# tmtr_board_rev1_1.net
KiCad netlist of a schematic drawn in Altium Designer
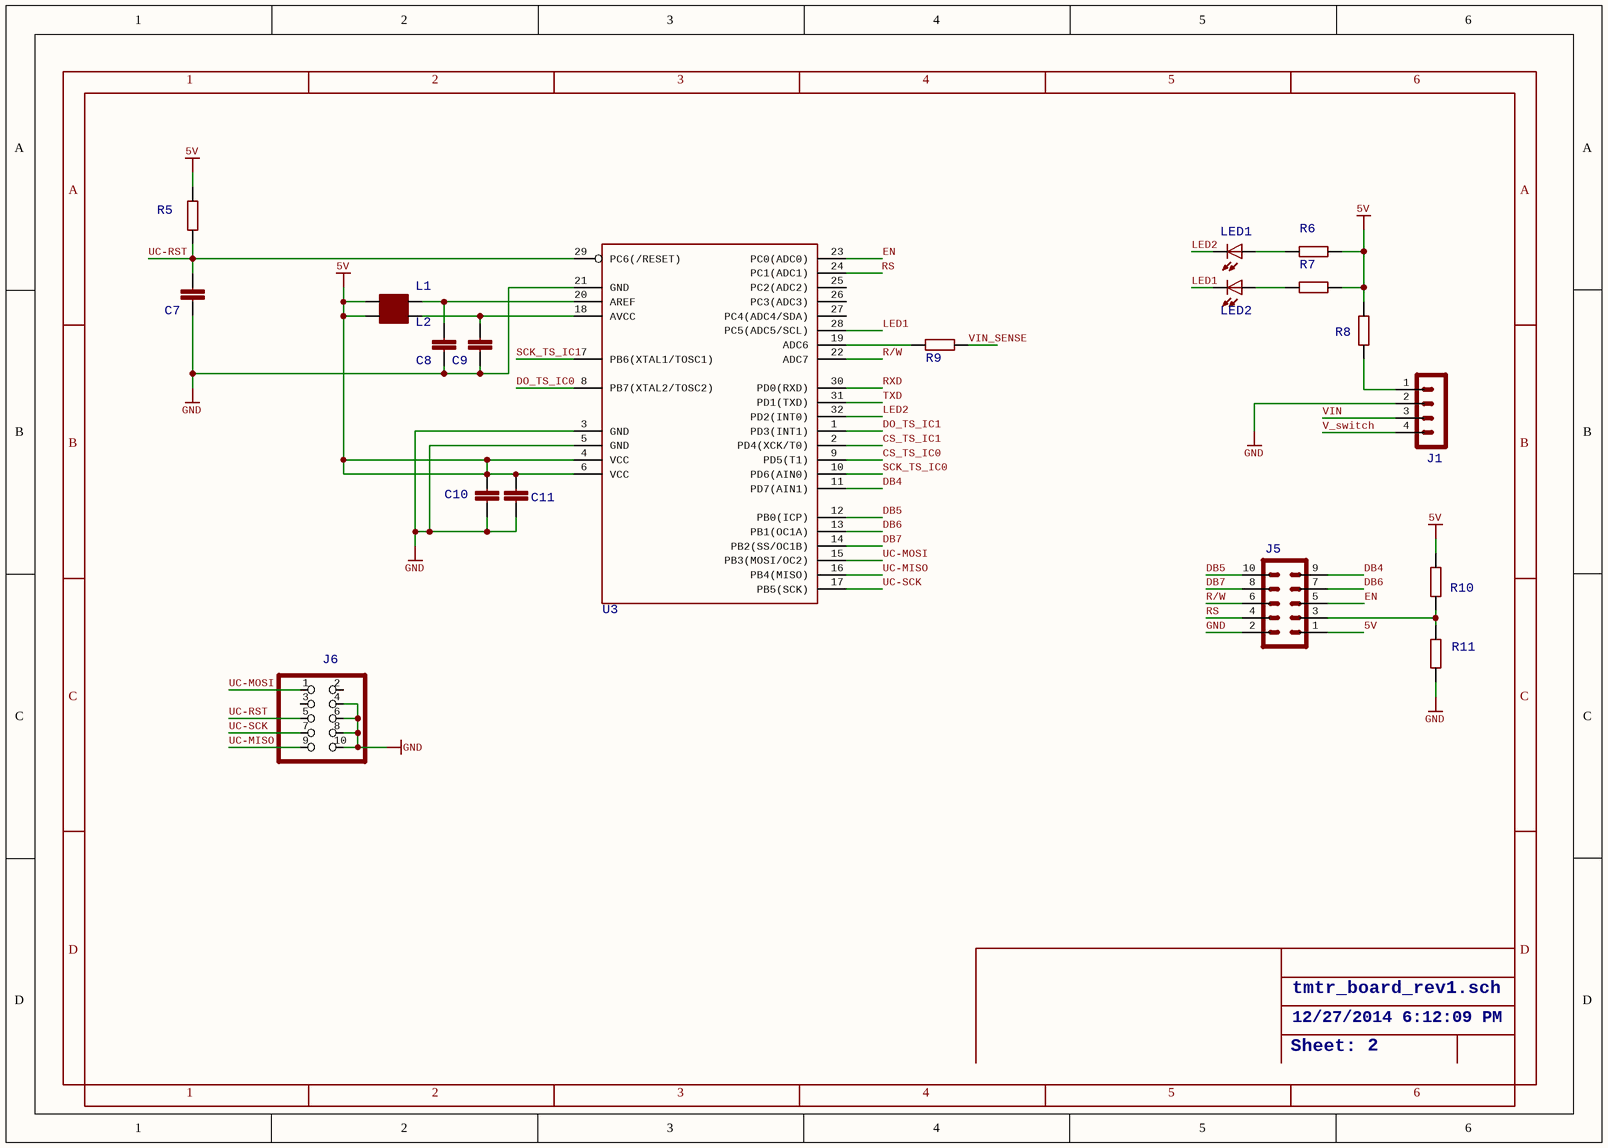
[diagram p0: tmtr_board_rev1_1.SchDoc]

(export (version "E")
  (design (tool "Eeschema 10.0.6"))
  (components
    (comp (ref "C7")
      (value "CAP0805")
      (footprint "0805")
      (description "<b>Capacitor</b>\nStandard 0603 ceramic capacitor, and 0.1\" leaded capacitor.")
      (libsource (lib "SparkFun1") (part "CAP0805"))
    )
    (comp (ref "C8")
      (value "CAP0805")
      (footprint "0805")
      (description "<b>Capacitor</b>\nStandard 0603 ceramic capacitor, and 0.1\" leaded capacitor.")
      (libsource (lib "SparkFun1") (part "CAP0805"))
    )
    (comp (ref "C9")
      (value "CAP0805")
      (footprint "0805")
      (description "<b>Capacitor</b>\nStandard 0603 ceramic capacitor, and 0.1\" leaded capacitor.")
      (libsource (lib "SparkFun1") (part "CAP0805"))
    )
    (comp (ref "C10")
      (value "CAP0805")
      (footprint "0805")
      (description "<b>Capacitor</b>\nStandard 0603 ceramic capacitor, and 0.1\" leaded capacitor.")
      (libsource (lib "SparkFun1") (part "CAP0805"))
    )
    (comp (ref "C11")
      (value "CAP0805")
      (footprint "0805")
      (description "<b>Capacitor</b>\nStandard 0603 ceramic capacitor, and 0.1\" leaded capacitor.")
      (libsource (lib "SparkFun1") (part "CAP0805"))
    )
    (comp (ref "J1")
      (value "<b>PIN HEADER</b>")
      (footprint "MA04-1")
      (libsource (lib "con-lstb") (part "MA04-1"))
    )
    (comp (ref "J5")
      (value "<b>PIN HEADER</b>")
      (footprint "MA05-2")
      (libsource (lib "con-lstb") (part "MA05-2"))
    )
    (comp (ref "J6")
      (value "AVR_SPI_PROG")
      (footprint "AVR_ICSP")
      (libsource (lib "SparkFun2") (part "AVR_SPI_PROG"))
    )
    (comp (ref "L1")
      (value "WE-CBF_0805")
      (footprint "0805")
      (libsource (lib "wuerth-elektronik") (part "WE-CBF_0805"))
    )
    (comp (ref "L2")
      (value "WE-CBF_0805")
      (footprint "0805")
      (libsource (lib "wuerth-elektronik") (part "WE-CBF_0805"))
    )
    (comp (ref "LED1")
      (value "LEDCHIPLED_0805")
      (footprint "CHIPLED_0805")
      (libsource (lib "led") (part "LEDCHIPLED_0805"))
    )
    (comp (ref "LED2")
      (value "LEDCHIPLED_0805")
      (footprint "CHIPLED_0805")
      (libsource (lib "led") (part "LEDCHIPLED_0805"))
    )
    (comp (ref "R5")
      (value "R-EU_R0805W")
      (footprint "R0805W")
      (description "<B>RESISTOR</B>, European symbol")
      (libsource (lib "resistor") (part "R-EU_R0805W"))
    )
    (comp (ref "R6")
      (value "R-EU_M0805")
      (footprint "M0805")
      (description "<B>RESISTOR</B>, European symbol")
      (libsource (lib "resistor") (part "R-EU_M0805"))
    )
    (comp (ref "R7")
      (value "R-EU_M0805")
      (footprint "M0805")
      (description "<B>RESISTOR</B>, European symbol")
      (libsource (lib "resistor") (part "R-EU_M0805"))
    )
    (comp (ref "R8")
      (value "R-EU_M0805")
      (footprint "M0805")
      (description "<B>RESISTOR</B>, European symbol")
      (libsource (lib "resistor") (part "R-EU_M0805"))
    )
    (comp (ref "R9")
      (value "R-EU_M0805")
      (footprint "M0805")
      (description "<B>RESISTOR</B>, European symbol")
      (libsource (lib "resistor") (part "R-EU_M0805"))
    )
    (comp (ref "R10")
      (value "R-EU_M0805")
      (footprint "M0805")
      (description "<B>RESISTOR</B>, European symbol")
      (libsource (lib "resistor") (part "R-EU_M0805"))
    )
    (comp (ref "R11")
      (value "R-EU_M0805")
      (footprint "M0805")
      (description "<B>RESISTOR</B>, European symbol")
      (libsource (lib "resistor") (part "R-EU_M0805"))
    )
    (comp (ref "U3") (value "MEGA8-AI") (footprint "TQFP32-08") (libsource (lib "atmel") (part "MEGA8-AI")))
  )
  (nets
    (net (code "1") (name "/CS_TS_IC0") (class "Default")
      (node (ref "U3") (pin "9") (pinfunction "PD5(T1)_9") (pintype "passive"))
    )
    (net (code "2") (name "/CS_TS_IC1") (class "Default")
      (node (ref "U3") (pin "2") (pinfunction "PD4(XCK/T0)_2") (pintype "passive"))
    )
    (net (code "3") (name "/DB4") (class "Default")
      (node (ref "J5") (pin "9") (pinfunction "9_9") (pintype "passive"))
      (node (ref "U3") (pin "11") (pinfunction "PD7(AIN1)_11") (pintype "passive"))
    )
    (net (code "4") (name "/DB5") (class "Default")
      (node (ref "J5") (pin "10") (pinfunction "10_10") (pintype "passive"))
      (node (ref "U3") (pin "12") (pinfunction "PB0(ICP)_12") (pintype "passive"))
    )
    (net (code "5") (name "/DB6") (class "Default")
      (node (ref "J5") (pin "7") (pinfunction "7_7") (pintype "passive"))
      (node (ref "U3") (pin "13") (pinfunction "PB1(OC1A)_13") (pintype "passive"))
    )
    (net (code "6") (name "/DB7") (class "Default")
      (node (ref "J5") (pin "8") (pinfunction "8_8") (pintype "passive"))
      (node (ref "U3") (pin "14") (pinfunction "PB2(SS/OC1B)_14") (pintype "passive"))
    )
    (net (code "7") (name "/DO_TS_IC0") (class "Default")
      (node (ref "U3") (pin "8") (pinfunction "PB7(XTAL2/TOSC2)_8") (pintype "passive"))
    )
    (net (code "8") (name "/DO_TS_IC1") (class "Default")
      (node (ref "U3") (pin "1") (pinfunction "PD3(INT1)_1") (pintype "passive"))
    )
    (net (code "9") (name "/EN") (class "Default")
      (node (ref "J5") (pin "5") (pinfunction "5_5") (pintype "passive"))
      (node (ref "U3") (pin "23") (pinfunction "PC0(ADC0)_23") (pintype "passive"))
    )
    (net (code "10") (name "/LED1") (class "Default")
      (node (ref "LED2") (pin "C") (pinfunction "C_C") (pintype "passive"))
      (node (ref "U3") (pin "28") (pinfunction "PC5(ADC5/SCL)_28") (pintype "passive"))
    )
    (net (code "11") (name "/LED2") (class "Default")
      (node (ref "LED1") (pin "C") (pinfunction "C_C") (pintype "passive"))
      (node (ref "U3") (pin "32") (pinfunction "PD2(INT0)_32") (pintype "passive"))
    )
    (net (code "12") (name "/RS") (class "Default")
      (node (ref "J5") (pin "4") (pinfunction "4_4") (pintype "passive"))
      (node (ref "U3") (pin "24") (pinfunction "PC1(ADC1)_24") (pintype "passive"))
    )
    (net (code "13") (name "/RXD") (class "Default")
      (node (ref "U3") (pin "30") (pinfunction "PD0(RXD)_30") (pintype "passive"))
    )
    (net (code "14") (name "/R{slash}W") (class "Default")
      (node (ref "J5") (pin "6") (pinfunction "6_6") (pintype "passive"))
      (node (ref "U3") (pin "22") (pinfunction "ADC7_22") (pintype "passive"))
    )
    (net (code "15") (name "/SCK_TS_IC0") (class "Default")
      (node (ref "U3") (pin "10") (pinfunction "PD6(AIN0)_10") (pintype "passive"))
    )
    (net (code "16") (name "/SCK_TS_IC1") (class "Default")
      (node (ref "U3") (pin "7") (pinfunction "PB6(XTAL1/TOSC1)_7") (pintype "passive"))
    )
    (net (code "17") (name "/TXD") (class "Default")
      (node (ref "U3") (pin "31") (pinfunction "PD1(TXD)_31") (pintype "passive"))
    )
    (net (code "18") (name "/UC-MISO") (class "Default")
      (node (ref "J6") (pin "9") (pinfunction "9_9") (pintype "passive"))
      (node (ref "U3") (pin "16") (pinfunction "PB4(MISO)_16") (pintype "passive"))
    )
    (net (code "19") (name "/UC-MOSI") (class "Default")
      (node (ref "J6") (pin "1") (pinfunction "1_1") (pintype "passive"))
      (node (ref "U3") (pin "15") (pinfunction "PB3(MOSI/OC2)_15") (pintype "passive"))
    )
    (net (code "20") (name "/UC-RST") (class "Default")
      (node (ref "C7") (pin "2") (pinfunction "2_2") (pintype "passive"))
      (node (ref "J6") (pin "5") (pinfunction "5_5") (pintype "passive"))
      (node (ref "R5") (pin "1") (pinfunction "1_1") (pintype "passive"))
      (node (ref "U3") (pin "29") (pinfunction "PC6(/RESET)_29") (pintype "passive"))
    )
    (net (code "21") (name "/UC-SCK") (class "Default")
      (node (ref "J6") (pin "7") (pinfunction "7_7") (pintype "passive"))
      (node (ref "U3") (pin "17") (pinfunction "PB5(SCK)_17") (pintype "passive"))
    )
    (net (code "22") (name "/VIN") (class "Default")
      (node (ref "J1") (pin "3") (pinfunction "3_3") (pintype "passive"))
    )
    (net (code "23") (name "/VIN_SENSE") (class "Default")
      (node (ref "R9") (pin "1") (pinfunction "1_1") (pintype "passive"))
    )
    (net (code "24") (name "/V_switch") (class "Default")
      (node (ref "J1") (pin "4") (pinfunction "4_4") (pintype "passive"))
    )
    (net (code "25") (name "5V") (class "Default")
      (node (ref "C10") (pin "2") (pinfunction "2_2") (pintype "passive"))
      (node (ref "C11") (pin "2") (pinfunction "2_2") (pintype "passive"))
      (node (ref "J5") (pin "1") (pinfunction "1_1") (pintype "passive"))
      (node (ref "L1") (pin "1") (pinfunction "1_1") (pintype "passive"))
      (node (ref "L2") (pin "1") (pinfunction "1_1") (pintype "passive"))
      (node (ref "R10") (pin "1") (pinfunction "1_1") (pintype "passive"))
      (node (ref "R5") (pin "2") (pinfunction "2_2") (pintype "passive"))
      (node (ref "R6") (pin "1") (pinfunction "1_1") (pintype "passive"))
      (node (ref "R7") (pin "1") (pinfunction "1_1") (pintype "passive"))
      (node (ref "R8") (pin "1") (pinfunction "1_1") (pintype "passive"))
      (node (ref "U3") (pin "4") (pinfunction "VCC_4") (pintype "power_in"))
      (node (ref "U3") (pin "6") (pinfunction "VCC_6") (pintype "power_in"))
    )
    (net (code "26") (name "GND") (class "Default")
      (node (ref "C10") (pin "1") (pinfunction "1_1") (pintype "passive"))
      (node (ref "C11") (pin "1") (pinfunction "1_1") (pintype "passive"))
      (node (ref "C7") (pin "1") (pinfunction "1_1") (pintype "passive"))
      (node (ref "C8") (pin "1") (pinfunction "1_1") (pintype "passive"))
      (node (ref "C9") (pin "1") (pinfunction "1_1") (pintype "passive"))
      (node (ref "J1") (pin "2") (pinfunction "2_2") (pintype "passive"))
      (node (ref "J5") (pin "2") (pinfunction "2_2") (pintype "passive"))
      (node (ref "J6") (pin "10") (pinfunction "10_10") (pintype "passive"))
      (node (ref "J6") (pin "4") (pinfunction "4_4") (pintype "passive"))
      (node (ref "J6") (pin "6") (pinfunction "6_6") (pintype "passive"))
      (node (ref "J6") (pin "8") (pinfunction "8_8") (pintype "passive"))
      (node (ref "R11") (pin "2") (pinfunction "2_2") (pintype "passive"))
      (node (ref "U3") (pin "21") (pinfunction "GND_21") (pintype "power_in"))
      (node (ref "U3") (pin "3") (pinfunction "GND_3") (pintype "power_in"))
      (node (ref "U3") (pin "5") (pinfunction "GND_5") (pintype "power_in"))
    )
    (net (code "27") (name "Net-(J1-Pad1)") (class "Default")
      (node (ref "J1") (pin "1") (pinfunction "1_1") (pintype "passive"))
      (node (ref "R8") (pin "2") (pinfunction "2_2") (pintype "passive"))
    )
    (net (code "28") (name "Net-(J5-Pad3)") (class "Default")
      (node (ref "J5") (pin "3") (pinfunction "3_3") (pintype "passive"))
      (node (ref "R10") (pin "2") (pinfunction "2_2") (pintype "passive"))
      (node (ref "R11") (pin "1") (pinfunction "1_1") (pintype "passive"))
    )
    (net (code "29") (name "Net-(LED1-PadA)") (class "Default")
      (node (ref "LED1") (pin "A") (pinfunction "A_A") (pintype "passive"))
      (node (ref "R6") (pin "2") (pinfunction "2_2") (pintype "passive"))
    )
    (net (code "30") (name "Net-(LED2-PadA)") (class "Default")
      (node (ref "LED2") (pin "A") (pinfunction "A_A") (pintype "passive"))
      (node (ref "R7") (pin "2") (pinfunction "2_2") (pintype "passive"))
    )
    (net (code "31") (name "Net-(U3-ADC6)") (class "Default")
      (node (ref "R9") (pin "2") (pinfunction "2_2") (pintype "passive"))
      (node (ref "U3") (pin "19") (pinfunction "ADC6_19") (pintype "passive"))
    )
    (net (code "32") (name "Net-(U3-AREF)") (class "Default")
      (node (ref "C8") (pin "2") (pinfunction "2_2") (pintype "passive"))
      (node (ref "L1") (pin "2") (pinfunction "2_2") (pintype "passive"))
      (node (ref "U3") (pin "20") (pinfunction "AREF_20") (pintype "passive"))
    )
    (net (code "33") (name "Net-(U3-AVCC)") (class "Default")
      (node (ref "C9") (pin "2") (pinfunction "2_2") (pintype "passive"))
      (node (ref "L2") (pin "2") (pinfunction "2_2") (pintype "passive"))
      (node (ref "U3") (pin "18") (pinfunction "AVCC_18") (pintype "power_in"))
    )
    (net (code "34") (name "unconnected-(J6-Pad2)") (class "Default")
      (node (ref "J6") (pin "2") (pinfunction "2_2") (pintype "passive"))
    )
    (net (code "35") (name "unconnected-(J6-Pad3)") (class "Default")
      (node (ref "J6") (pin "3") (pinfunction "3_3") (pintype "passive"))
    )
    (net (code "36") (name "unconnected-(U3-PC2(ADC2)-Pad25)") (class "Default")
      (node (ref "U3") (pin "25") (pinfunction "PC2(ADC2)_25") (pintype "passive"))
    )
    (net (code "37") (name "unconnected-(U3-PC3(ADC3)-Pad26)") (class "Default")
      (node (ref "U3") (pin "26") (pinfunction "PC3(ADC3)_26") (pintype "passive"))
    )
    (net (code "38") (name "unconnected-(U3-PC4(ADC4{slash}SDA)-Pad27)") (class "Default")
      (node (ref "U3") (pin "27") (pinfunction "PC4(ADC4/SDA)_27") (pintype "passive"))
    )
  )
)
